# Inverter.net
KiCad netlist of a schematic drawn in EAGLE
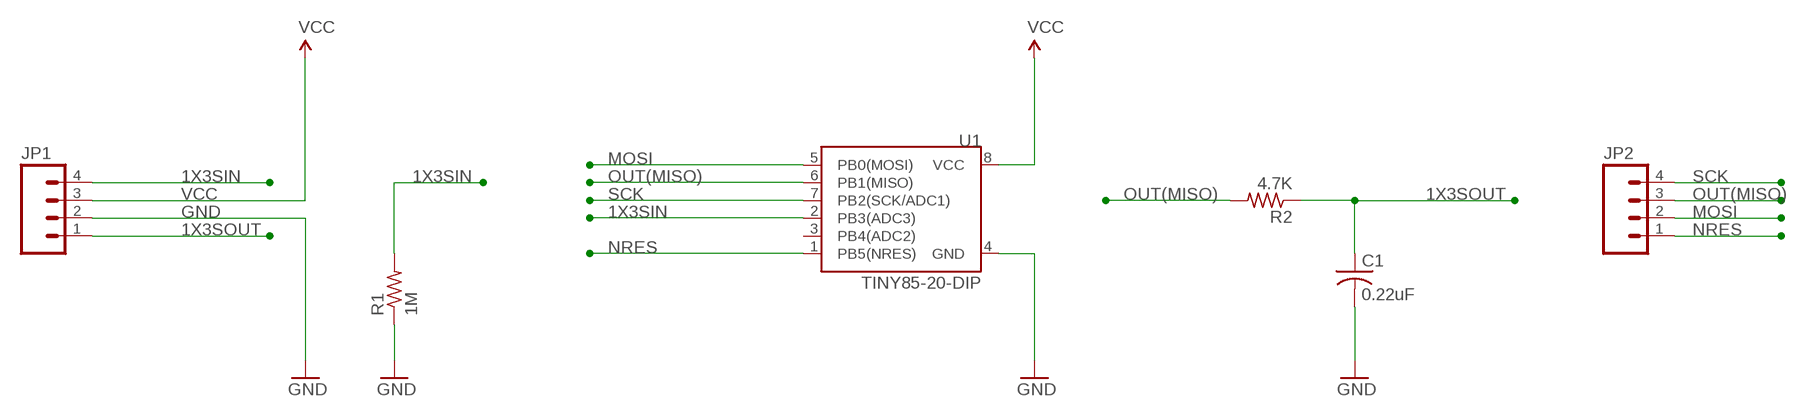
[diagram p0: schematic, sheet 1]

(export (version "E")
  (design (tool "Eeschema 10.0.6"))
  (components
    (comp (ref "C1")
      (value "0.22uF")
      (footprint "eagle-import:C0603")
      (libsource (lib "eagle-import") (part "C-USC0603"))
    )
    (comp (ref "JP1")
      (value "M04PTH")
      (footprint "eagle-import:1X04")
      (libsource (lib "eagle-import") (part "M04PTH"))
    )
    (comp (ref "JP2")
      (value "M04PTH")
      (footprint "eagle-import:1X04")
      (libsource (lib "eagle-import") (part "M04PTH"))
    )
    (comp (ref "R1")
      (value "1M")
      (footprint "eagle-import:R0603")
      (libsource (lib "eagle-import") (part "R-US_R0603"))
    )
    (comp (ref "R2")
      (value "4.7K")
      (footprint "eagle-import:R0603")
      (libsource (lib "eagle-import") (part "R-US_R0603"))
    )
    (comp (ref "U1")
      (value "TINY85-20-DIP")
      (footprint "eagle-import:DIP08")
      (libsource (lib "eagle-import") (part "ATTINY45TINY85-20-DIP"))
    )
  )
  (nets
    (net (code "1") (name "/1X3SIN") (class "Default")
      (node (ref "JP1") (pin "4") (pinfunction "4_4") (pintype "passive"))
      (node (ref "R1") (pin "2") (pinfunction "2_2") (pintype "passive"))
      (node (ref "U1") (pin "2") (pinfunction "PB3(ADC3)_2") (pintype "bidirectional"))
    )
    (net (code "2") (name "/1X3SOUT") (class "Default")
      (node (ref "C1") (pin "1") (pinfunction "1_1") (pintype "passive"))
      (node (ref "JP1") (pin "1") (pinfunction "1_1") (pintype "passive"))
      (node (ref "R2") (pin "1") (pinfunction "1_1") (pintype "passive"))
    )
    (net (code "3") (name "/MOSI") (class "Default")
      (node (ref "JP2") (pin "2") (pinfunction "2_2") (pintype "passive"))
      (node (ref "U1") (pin "5") (pinfunction "PB0(MOSI)_5") (pintype "bidirectional"))
    )
    (net (code "4") (name "/NRES") (class "Default")
      (node (ref "JP2") (pin "1") (pinfunction "1_1") (pintype "passive"))
      (node (ref "U1") (pin "1") (pinfunction "PB5(NRES)_1") (pintype "bidirectional"))
    )
    (net (code "5") (name "/OUT(MISO)") (class "Default")
      (node (ref "JP2") (pin "3") (pinfunction "3_3") (pintype "passive"))
      (node (ref "R2") (pin "2") (pinfunction "2_2") (pintype "passive"))
      (node (ref "U1") (pin "6") (pinfunction "PB1(MISO)_6") (pintype "bidirectional"))
    )
    (net (code "6") (name "/SCK") (class "Default")
      (node (ref "JP2") (pin "4") (pinfunction "4_4") (pintype "passive"))
      (node (ref "U1") (pin "7") (pinfunction "PB2(SCK/ADC1)_7") (pintype "bidirectional"))
    )
    (net (code "7") (name "GND") (class "Default")
      (node (ref "C1") (pin "2") (pinfunction "2_2") (pintype "passive"))
      (node (ref "JP1") (pin "2") (pinfunction "2_2") (pintype "passive"))
      (node (ref "R1") (pin "1") (pinfunction "1_1") (pintype "passive"))
      (node (ref "U1") (pin "4") (pinfunction "GND_4") (pintype "bidirectional"))
    )
    (net (code "8") (name "VCC") (class "Default")
      (node (ref "JP1") (pin "3") (pinfunction "3_3") (pintype "passive"))
      (node (ref "U1") (pin "8") (pinfunction "VCC_8") (pintype "bidirectional"))
    )
    (net (code "9") (name "unconnected-(U1-PB4(ADC2)-Pad3)") (class "Default")
      (node (ref "U1") (pin "3") (pinfunction "PB4(ADC2)_3") (pintype "bidirectional"))
    )
  )
)
